# tsop.net
KiCad netlist of a schematic drawn in Altium Designer
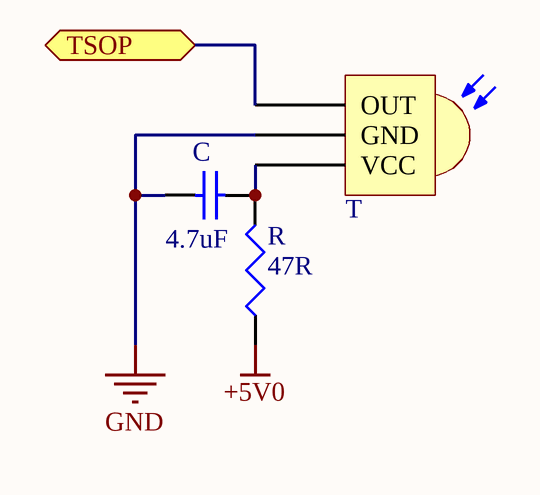
[diagram p0: tsop.SchDoc]

(export (version "E")
  (design (tool "Eeschema 10.0.6"))
  (components
    (comp (ref "C")
      (value "4.7uF")
      (footprint "C0805C")
      (description "Capacitor")
      (fields (field (name "Comment") "CAP") (field (name "PUBLISHER") "Altium Limited"))
      (libsource (lib "7Robot") (part "CAP"))
    )
    (comp (ref "R")
      (value "47R")
      (footprint "C0805R")
      (description "Resistor")
      (fields (field (name "Comment") "RES") (field (name "PUBLISHER") "Altium Limited"))
      (libsource (lib "7Robot") (part "RES"))
    )
    (comp (ref "T")
      (value "TSOP7000")
      (footprint "TSOP IR")
      (description "Vishay 455kHz IR Receiver")
      (libsource (lib "7Robot") (part "TSOP7000"))
    )
  )
  (nets
    (net (code "1") (name "+5V0") (class "Default")
      (node (ref "R") (pin "1") (pinfunction "1_1") (pintype "passive"))
    )
    (net (code "2") (name "/TSOP") (class "Default")
      (node (ref "T") (pin "1") (pinfunction "OUT_1") (pintype "passive"))
    )
    (net (code "3") (name "GND") (class "Default")
      (node (ref "C") (pin "2") (pinfunction "2_2") (pintype "passive"))
      (node (ref "T") (pin "2") (pinfunction "GND_2") (pintype "power_in"))
    )
    (net (code "4") (name "Net-(T-VCC)") (class "Default")
      (node (ref "C") (pin "1") (pinfunction "1_1") (pintype "passive"))
      (node (ref "R") (pin "2") (pinfunction "2_2") (pintype "passive"))
      (node (ref "T") (pin "3") (pinfunction "VCC_3") (pintype "power_in"))
    )
  )
)
